# power_supply.net
KiCad netlist of a schematic drawn in Altium Designer
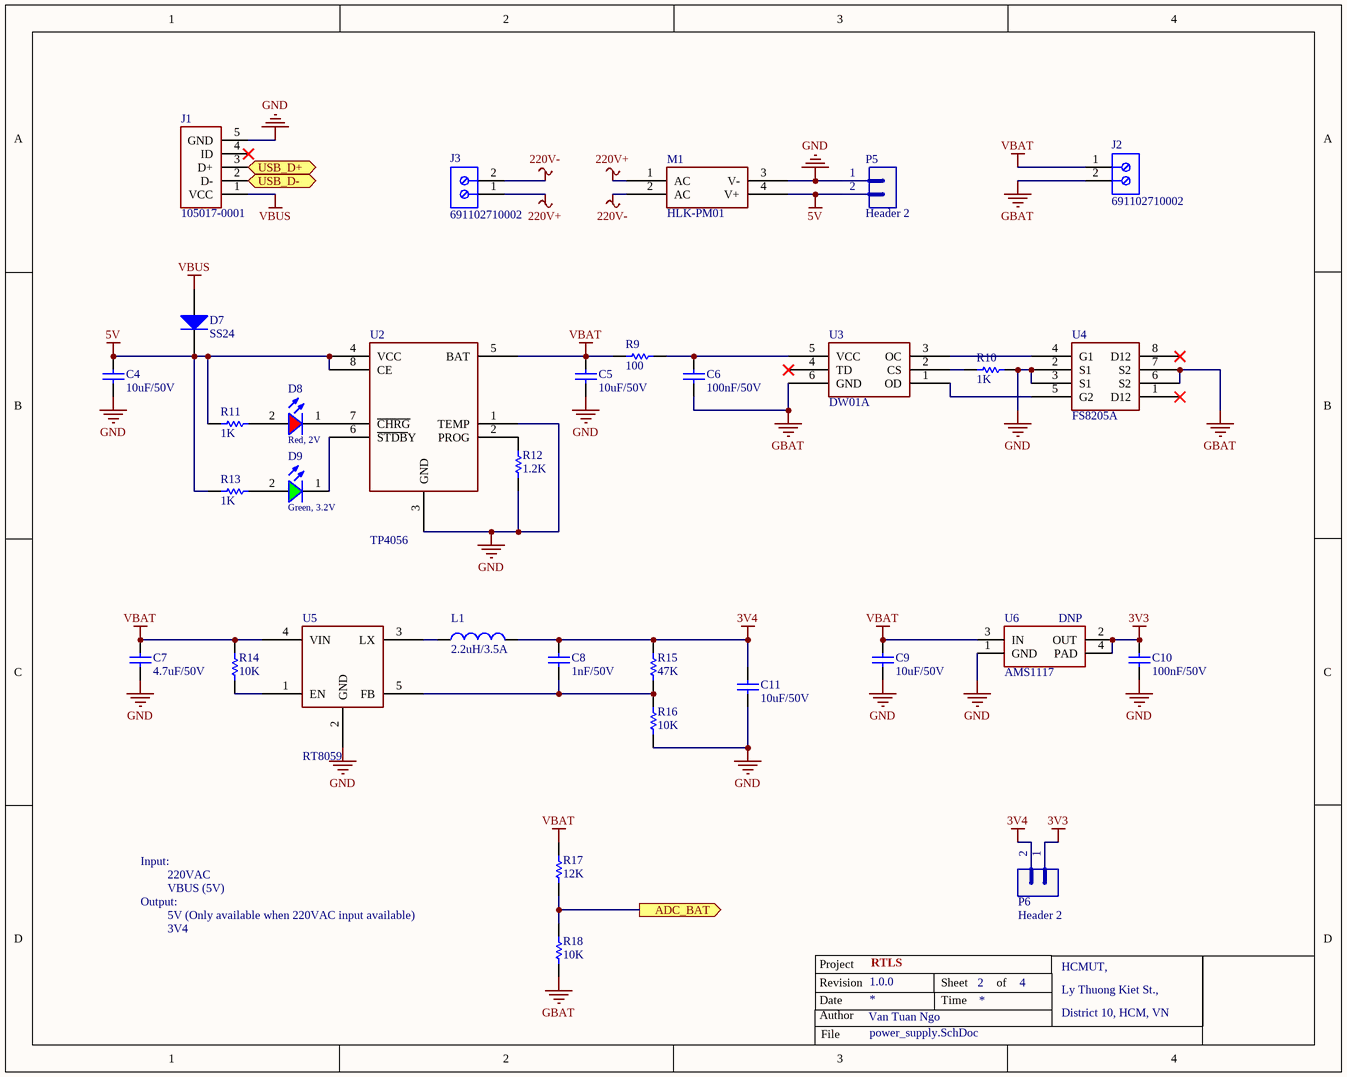
[diagram p0: power_supply.SchDoc]

(export (version "E")
  (design (tool "Eeschema 10.0.6"))
  (components
    (comp (ref "C4")
      (value "10uF/50V")
      (footprint "CAP-SM-0805")
      (description "CAP CER 10UF 50V X5R 0805")
      (fields
        (field (name "MANUFACTURER") "Yageo")
        (field (name "MANUFACTURER PART NUMBER") "CC0805KKX5R9BB106")
      )
      (libsource (lib "capacitor-smd") (part "Cap-10uF-50V-0805"))
    )
    (comp (ref "C5")
      (value "10uF/50V")
      (footprint "CAP-SM-0805")
      (description "CAP CER 10UF 50V X5R 0805")
      (fields
        (field (name "MANUFACTURER") "Yageo")
        (field (name "MANUFACTURER PART NUMBER") "CC0805KKX5R9BB106")
      )
      (libsource (lib "capacitor-smd") (part "Cap-10uF-50V-0805"))
    )
    (comp (ref "C6")
      (value "100nF/50V")
      (footprint "CAP-SM-0805")
      (description "CAP CER 0.1UF 50V Y5V 0805")
      (fields
        (field (name "MANUFACTURER") "Samsung Electro-Mechanics")
        (field (name "MANUFACTURER PART NUMBER") "CL21F104ZBCNNNC")
      )
      (libsource (lib "capacitor-smd") (part "Cap-100nF-50V-0805"))
    )
    (comp (ref "C7")
      (value "4.7uF/50V")
      (footprint "CAP-SM-0805")
      (description "CAP CER 4.7UF 50V X5R 0805")
      (fields
        (field (name "MANUFACTURER") "Murata Electronics")
        (field (name "MANUFACTURER PART NUMBER") "GRM21BR61H475KE51L")
      )
      (libsource (lib "capacitor-smd") (part "Cap-4.7uF-50V-0805"))
    )
    (comp (ref "C8")
      (value "1nF/50V")
      (footprint "CAP-SM-0805")
      (description "CAP CER 22PF 100V X7R 0805")
      (fields
        (field (name "MANUFACTURER") "Johanson Dielectrics Inc.")
        (field (name "MANUFACTURER PART NUMBER") "101X15W102MV4E")
      )
      (libsource (lib "capacitor-smd") (part "Cap-22pF-50V-0805"))
    )
    (comp (ref "C9")
      (value "10uF/50V")
      (footprint "CAP-SM-0805")
      (description "CAP CER 10UF 50V X5R 0805")
      (fields
        (field (name "MANUFACTURER") "Yageo")
        (field (name "MANUFACTURER PART NUMBER") "CC0805KKX5R9BB106")
      )
      (libsource (lib "capacitor-smd") (part "Cap-10uF-50V-0805"))
    )
    (comp (ref "C10")
      (value "100nF/50V")
      (footprint "CAP-SM-0805")
      (description "CAP CER 0.1UF 50V Y5V 0805")
      (fields
        (field (name "MANUFACTURER") "Samsung Electro-Mechanics")
        (field (name "MANUFACTURER PART NUMBER") "CL21F104ZBCNNNC")
      )
      (libsource (lib "capacitor-smd") (part "Cap-100nF-50V-0805"))
    )
    (comp (ref "C11")
      (value "10uF/50V")
      (footprint "CAP-SM-0805")
      (description "CAP CER 10UF 50V X5R 0805")
      (fields
        (field (name "MANUFACTURER") "Yageo")
        (field (name "MANUFACTURER PART NUMBER") "CC0805KKX5R9BB106")
      )
      (libsource (lib "capacitor-smd") (part "Cap-10uF-50V-0805"))
    )
    (comp (ref "D7")
      (value "SS24")
      (footprint "SS24")
      (description "DIODE SCHOTTKY 40V 2A DO214AA")
      (fields (field (name "MANUFACTURER") "ON Semiconductor"))
      (libsource (lib "diode-smd") (part "Diode-SS24"))
    )
    (comp (ref "D8")
      (value "Red, 2V")
      (footprint "WL-SMCW_0805")
      (description "WL-SMCW SMT Mono-color Chip LED Waterclear, size 0805, Red, 2V, 140deg")
      (fields (field (name "PART NUMBER") "150080RS75000") (field (name "PUBLISHER") "Wurth Elektronik"))
      (libsource (lib "led-smd-0805") (part "150080RS75000"))
    )
    (comp (ref "D9")
      (value "Green, 3.2V")
      (footprint "WL-SMCW_0805")
      (description "WL-SMCW SMT Mono-color Chip LED Waterclear, size 0805, Green, 3.2V, 140deg")
      (fields (field (name "PART NUMBER") "150080GS75000") (field (name "PUBLISHER") "Wurth Elektronik"))
      (libsource (lib "led-smd-0805") (part "150080GS75000"))
    )
    (comp (ref "J1")
      (value "105017-0001")
      (footprint "Micro-USB-Female")
      (description "CONN RCPT USB2.0 MICRO B SMD R/A")
      (fields
        (field (name "LOCAL SUPPLIER PART NUMBER") "x")
        (field (name "COPYRIGHT") "Copyright (C) 2018 Accelerated Designs. All rights reserved")
      )
      (libsource (lib "header-connector") (part "Micro-USB-Female"))
    )
    (comp (ref "J2")
      (value "691102710002")
      (footprint "691102710002")
      (description "WR-TBL Serie 102 Horizontal Entry Modular, Pressure Clamp, pitch 5mm, 2p")
      (fields (field (name "PUBLISHER") "Wurth Elektronik"))
      (libsource (lib "domino-wire-protector") (part "691102710002"))
    )
    (comp (ref "J3")
      (value "691102710002")
      (footprint "691102710002")
      (description "WR-TBL Serie 102 Horizontal Entry Modular, Pressure Clamp, pitch 5mm, 2p")
      (fields (field (name "PUBLISHER") "Wurth Elektronik"))
      (libsource (lib "WR-TBL_Wire Protector") (part "691102710002"))
    )
    (comp (ref "L1")
      (value "2.2uH/3.5A")
      (footprint "CD53")
      (libsource (lib "inductor-smd") (part "ind-2.2uH-3.5A-CD53"))
    )
    (comp (ref "M1")
      (value "HLK-PM01")
      (footprint "HLK-PM01")
      (libsource (lib "power-ic-module") (part "HLK-PM01"))
    )
    (comp (ref "P5")
      (value "Header 2")
      (footprint "JP2")
      (description "Header, 2-Pin")
      (fields (field (name "LOCAL SUPPLIER PART NUMBER") "x") (field (name "PUBLISHER") "Altium Limited"))
      (libsource (lib "header-connector") (part "Header 2"))
    )
    (comp (ref "P6")
      (value "Header 2")
      (footprint "JP2")
      (description "Header, 2-Pin")
      (fields (field (name "LOCAL SUPPLIER PART NUMBER") "x") (field (name "PUBLISHER") "Altium Limited"))
      (libsource (lib "") (part "Header 2_1"))
    )
    (comp (ref "R9")
      (value "100")
      (footprint "resistor-smd:RES-SM-0805")
      (description "RES 100 OHM 0.1% 1/5W 0805")
      (fields
        (field (name "MANUFACTURER") "Vishay Thin Film")
        (field (name "MANUFACTURER PART NUMBER") "PTN0805E10R0BST1")
      )
      (libsource (lib "resistor-smd") (part "Res-100-0805"))
    )
    (comp (ref "R10")
      (value "1K")
      (footprint "resistor-smd:RES-SM-0805")
      (description "RES 1K OHM 1% 1/4W 0805")
      (fields
        (field (name "MANUFACTURER") "Stackpole Electronics Inc")
        (field (name "MANUFACTURER PART NUMBER") "RNCP0805FTD1K00")
      )
      (libsource (lib "resistor-smd") (part "Res-1K-0805"))
    )
    (comp (ref "R11")
      (value "1K")
      (footprint "resistor-smd:RES-SM-0805")
      (description "RES 1K OHM 1% 1/4W 0805")
      (fields
        (field (name "MANUFACTURER") "Stackpole Electronics Inc")
        (field (name "MANUFACTURER PART NUMBER") "RNCP0805FTD1K00")
      )
      (libsource (lib "resistor-smd") (part "Res-1K-0805"))
    )
    (comp (ref "R12")
      (value "1.2K")
      (footprint "resistor-smd:RES-SM-0805")
      (description "RES SMD 1.2K OHM 1% 1/8W 0805")
      (fields
        (field (name "MANUFACTURER") "TE Connectivity Passive Product")
        (field (name "MANUFACTURER PART NUMBER") "CRG0805F1K2")
      )
      (libsource (lib "resistor-smd") (part "Res-1.2K-0805"))
    )
    (comp (ref "R13")
      (value "1K")
      (footprint "resistor-smd:RES-SM-0805")
      (description "RES 1K OHM 1% 1/4W 0805")
      (fields
        (field (name "MANUFACTURER") "Stackpole Electronics Inc")
        (field (name "MANUFACTURER PART NUMBER") "RNCP0805FTD1K00")
      )
      (libsource (lib "resistor-smd") (part "Res-1K-0805"))
    )
    (comp (ref "R14")
      (value "10K")
      (footprint "resistor-smd:RES-SM-0805")
      (description "RES 10K OHM 1% 1/4W 0805")
      (fields
        (field (name "MANUFACTURER") "Stackpole Electronics Inc")
        (field (name "MANUFACTURER PART NUMBER") "RNCP0805FTD10K0")
      )
      (libsource (lib "resistor-smd") (part "Res-10k-0805"))
    )
    (comp (ref "R15")
      (value "47K")
      (footprint "resistor-smd:RES-SM-0805")
      (description "RES SMD 47K OHM 1% 1/8W 0805")
      (fields
        (field (name "MANUFACTURER") "Yageo")
        (field (name "MANUFACTURER PART NUMBER") "RC0805FR-0747KL")
      )
      (libsource (lib "resistor-smd") (part "Res-47K-0805"))
    )
    (comp (ref "R16")
      (value "10K")
      (footprint "resistor-smd:RES-SM-0805")
      (description "RES 10K OHM 1% 1/4W 0805")
      (fields
        (field (name "MANUFACTURER") "Stackpole Electronics Inc")
        (field (name "MANUFACTURER PART NUMBER") "RNCP0805FTD10K0")
      )
      (libsource (lib "resistor-smd") (part "Res-10k-0805"))
    )
    (comp (ref "R17")
      (value "12K")
      (footprint "resistor-smd:RES-SM-0805")
      (description "RES 12 KOHM JUMPER 0805")
      (fields
        (field (name "MANUFACTURER") "Vishay Thin Film")
        (field (name "MANUFACTURER PART NUMBER") "PAT0805E3121BST1")
      )
      (libsource (lib "resistor-smd") (part "Res-12K-0805"))
    )
    (comp (ref "R18")
      (value "10K")
      (footprint "resistor-smd:RES-SM-0805")
      (description "RES 10K OHM 1% 1/4W 0805")
      (fields
        (field (name "MANUFACTURER") "Stackpole Electronics Inc")
        (field (name "MANUFACTURER PART NUMBER") "RNCP0805FTD10K0")
      )
      (libsource (lib "resistor-smd") (part "Res-10k-0805"))
    )
    (comp (ref "U2")
      (value "TP4056")
      (footprint "SOP8")
      (description "Linear charger for single cell\r\nlithium-ion batteries")
      (libsource (lib "power-ic-module") (part "TP4056"))
    )
    (comp (ref "U3")
      (value "DW01A")
      (footprint "SOT-23-6")
      (description "Battery protection IC")
      (libsource (lib "power-ic-module") (part "DW01A"))
    )
    (comp (ref "U4") (value "FS8205A") (footprint "TSSOP8") (libsource (lib "mosfet-smd") (part "FS8205A")))
    (comp (ref "U5")
      (value "RT8059")
      (footprint "SOT-23-5")
      (description "High efficiency PWM step-down DC/DC converter")
      (libsource (lib "power-ic-module") (part "RT8059"))
    )
    (comp (ref "U6")
      (value "AMS1117")
      (footprint "SOT223")
      (description "Available in 1.8V, 2.5V, 2.85V, 3.3V, 5V, and  Adjustable Versions")
      (libsource (lib "power-ic-module") (part "AMS1117"))
    )
  )
  (nets
    (net (code "1") (name "/ADC_BAT") (class "Default")
      (node (ref "R17") (pin "1") (pinfunction "1_1") (pintype "passive"))
      (node (ref "R18") (pin "2") (pinfunction "2_2") (pintype "passive"))
    )
    (net (code "2") (name "/USB_D+") (class "Default")
      (node (ref "J1") (pin "3") (pinfunction "D+_3") (pintype "passive"))
    )
    (net (code "3") (name "/USB_D-") (class "Default")
      (node (ref "J1") (pin "2") (pinfunction "D-_2") (pintype "passive"))
    )
    (net (code "4") (name "3V3") (class "Default")
      (node (ref "C10") (pin "2") (pinfunction "2_2") (pintype "passive"))
      (node (ref "P6") (pin "1") (pinfunction "1_1") (pintype "passive"))
      (node (ref "U6") (pin "2") (pinfunction "OUT_2") (pintype "passive"))
      (node (ref "U6") (pin "4") (pinfunction "PAD_4") (pintype "passive"))
    )
    (net (code "5") (name "3V4") (class "Default")
      (node (ref "C11") (pin "2") (pinfunction "2_2") (pintype "passive"))
      (node (ref "C8") (pin "2") (pinfunction "2_2") (pintype "passive"))
      (node (ref "L1") (pin "2") (pinfunction "2_2") (pintype "passive"))
      (node (ref "P6") (pin "2") (pinfunction "2_2") (pintype "passive"))
      (node (ref "R15") (pin "2") (pinfunction "2_2") (pintype "passive"))
    )
    (net (code "6") (name "5V") (class "Default")
      (node (ref "C4") (pin "2") (pinfunction "2_2") (pintype "passive"))
      (node (ref "D7") (pin "1") (pinfunction "K_1") (pintype "passive"))
      (node (ref "M1") (pin "4") (pinfunction "V+_4") (pintype "passive"))
      (node (ref "P5") (pin "2") (pinfunction "2_2") (pintype "passive"))
      (node (ref "R11") (pin "1") (pinfunction "1_1") (pintype "passive"))
      (node (ref "R13") (pin "1") (pinfunction "1_1") (pintype "passive"))
      (node (ref "U2") (pin "4") (pinfunction "VCC_4") (pintype "passive"))
      (node (ref "U2") (pin "8") (pinfunction "CE_8") (pintype "passive"))
    )
    (net (code "7") (name "220V+") (class "Default")
      (node (ref "J3") (pin "1") (pinfunction "1_1") (pintype "passive"))
      (node (ref "M1") (pin "1") (pinfunction "AC_1") (pintype "passive"))
    )
    (net (code "8") (name "220V-") (class "Default")
      (node (ref "J3") (pin "2") (pinfunction "2_2") (pintype "passive"))
      (node (ref "M1") (pin "2") (pinfunction "AC_2") (pintype "passive"))
    )
    (net (code "9") (name "GBAT") (class "Default")
      (node (ref "C6") (pin "1") (pinfunction "1_1") (pintype "passive"))
      (node (ref "J2") (pin "2") (pinfunction "2_2") (pintype "passive"))
      (node (ref "R18") (pin "1") (pinfunction "1_1") (pintype "passive"))
      (node (ref "U3") (pin "6") (pinfunction "GND_6") (pintype "passive"))
      (node (ref "U4") (pin "6") (pinfunction "S2_6") (pintype "passive"))
      (node (ref "U4") (pin "7") (pinfunction "S2_7") (pintype "passive"))
    )
    (net (code "10") (name "GND") (class "Default")
      (node (ref "C10") (pin "1") (pinfunction "1_1") (pintype "passive"))
      (node (ref "C11") (pin "1") (pinfunction "1_1") (pintype "passive"))
      (node (ref "C4") (pin "1") (pinfunction "1_1") (pintype "passive"))
      (node (ref "C5") (pin "1") (pinfunction "1_1") (pintype "passive"))
      (node (ref "C7") (pin "1") (pinfunction "1_1") (pintype "passive"))
      (node (ref "C9") (pin "1") (pinfunction "1_1") (pintype "passive"))
      (node (ref "J1") (pin "5") (pinfunction "GND_5") (pintype "passive"))
      (node (ref "M1") (pin "3") (pinfunction "V-_3") (pintype "passive"))
      (node (ref "P5") (pin "1") (pinfunction "1_1") (pintype "passive"))
      (node (ref "R10") (pin "2") (pinfunction "2_2") (pintype "passive"))
      (node (ref "R12") (pin "1") (pinfunction "1_1") (pintype "passive"))
      (node (ref "R16") (pin "1") (pinfunction "1_1") (pintype "passive"))
      (node (ref "U2") (pin "1") (pinfunction "TEMP_1") (pintype "passive"))
      (node (ref "U2") (pin "3") (pinfunction "GND_3") (pintype "passive"))
      (node (ref "U4") (pin "2") (pinfunction "S1_2") (pintype "passive"))
      (node (ref "U4") (pin "3") (pinfunction "S1_3") (pintype "passive"))
      (node (ref "U5") (pin "2") (pinfunction "GND_2") (pintype "passive"))
      (node (ref "U6") (pin "1") (pinfunction "GND_1") (pintype "passive"))
    )
    (net (code "11") (name "Net-(D8-A)") (class "Default")
      (node (ref "D8") (pin "2") (pinfunction "A_2") (pintype "passive"))
      (node (ref "R11") (pin "2") (pinfunction "2_2") (pintype "passive"))
    )
    (net (code "12") (name "Net-(D8-K)") (class "Default")
      (node (ref "D8") (pin "1") (pinfunction "K_1") (pintype "passive"))
      (node (ref "U2") (pin "7") (pinfunction "~{CHRG}_7") (pintype "passive"))
    )
    (net (code "13") (name "Net-(D9-A)") (class "Default")
      (node (ref "D9") (pin "2") (pinfunction "A_2") (pintype "passive"))
      (node (ref "R13") (pin "2") (pinfunction "2_2") (pintype "passive"))
    )
    (net (code "14") (name "Net-(D9-K)") (class "Default")
      (node (ref "D9") (pin "1") (pinfunction "K_1") (pintype "passive"))
      (node (ref "U2") (pin "6") (pinfunction "~{STDB}Y_6") (pintype "passive"))
    )
    (net (code "15") (name "Net-(U2-PROG)") (class "Default")
      (node (ref "R12") (pin "2") (pinfunction "2_2") (pintype "passive"))
      (node (ref "U2") (pin "2") (pinfunction "PROG_2") (pintype "passive"))
    )
    (net (code "16") (name "Net-(U3-CS)") (class "Default")
      (node (ref "R10") (pin "1") (pinfunction "1_1") (pintype "passive"))
      (node (ref "U3") (pin "2") (pinfunction "CS_2") (pintype "passive"))
    )
    (net (code "17") (name "Net-(U3-OC)") (class "Default")
      (node (ref "U3") (pin "3") (pinfunction "OC_3") (pintype "passive"))
      (node (ref "U4") (pin "4") (pinfunction "G1_4") (pintype "passive"))
    )
    (net (code "18") (name "Net-(U3-OD)") (class "Default")
      (node (ref "U3") (pin "1") (pinfunction "OD_1") (pintype "passive"))
      (node (ref "U4") (pin "5") (pinfunction "G2_5") (pintype "passive"))
    )
    (net (code "19") (name "Net-(U3-VCC)") (class "Default")
      (node (ref "C6") (pin "2") (pinfunction "2_2") (pintype "passive"))
      (node (ref "R9") (pin "2") (pinfunction "2_2") (pintype "passive"))
      (node (ref "U3") (pin "5") (pinfunction "VCC_5") (pintype "passive"))
    )
    (net (code "20") (name "Net-(U5-EN)") (class "Default")
      (node (ref "R14") (pin "1") (pinfunction "1_1") (pintype "passive"))
      (node (ref "U5") (pin "1") (pinfunction "EN_1") (pintype "passive"))
    )
    (net (code "21") (name "Net-(U5-FB)") (class "Default")
      (node (ref "C8") (pin "1") (pinfunction "1_1") (pintype "passive"))
      (node (ref "R15") (pin "1") (pinfunction "1_1") (pintype "passive"))
      (node (ref "R16") (pin "2") (pinfunction "2_2") (pintype "passive"))
      (node (ref "U5") (pin "5") (pinfunction "FB_5") (pintype "passive"))
    )
    (net (code "22") (name "Net-(U5-LX)") (class "Default")
      (node (ref "L1") (pin "1") (pinfunction "1_1") (pintype "passive"))
      (node (ref "U5") (pin "3") (pinfunction "LX_3") (pintype "passive"))
    )
    (net (code "23") (name "VBAT") (class "Default")
      (node (ref "C5") (pin "2") (pinfunction "2_2") (pintype "passive"))
      (node (ref "C7") (pin "2") (pinfunction "2_2") (pintype "passive"))
      (node (ref "C9") (pin "2") (pinfunction "2_2") (pintype "passive"))
      (node (ref "J2") (pin "1") (pinfunction "1_1") (pintype "passive"))
      (node (ref "R14") (pin "2") (pinfunction "2_2") (pintype "passive"))
      (node (ref "R17") (pin "2") (pinfunction "2_2") (pintype "passive"))
      (node (ref "R9") (pin "1") (pinfunction "1_1") (pintype "passive"))
      (node (ref "U2") (pin "5") (pinfunction "BAT_5") (pintype "passive"))
      (node (ref "U5") (pin "4") (pinfunction "VIN_4") (pintype "passive"))
      (node (ref "U6") (pin "3") (pinfunction "IN_3") (pintype "passive"))
    )
    (net (code "24") (name "VBUS") (class "Default")
      (node (ref "D7") (pin "2") (pinfunction "A_2") (pintype "passive"))
      (node (ref "J1") (pin "1") (pinfunction "VCC_1") (pintype "power_in"))
    )
    (net (code "25") (name "unconnected-(J1-ID-Pad4)") (class "Default")
      (node (ref "J1") (pin "4") (pinfunction "ID_4") (pintype "passive+no_connect"))
    )
    (net (code "26") (name "unconnected-(U3-TD-Pad4)") (class "Default")
      (node (ref "U3") (pin "4") (pinfunction "TD_4") (pintype "passive+no_connect"))
    )
    (net (code "27") (name "unconnected-(U4-D12-Pad1)") (class "Default")
      (node (ref "U4") (pin "1") (pinfunction "D12_1") (pintype "passive+no_connect"))
    )
    (net (code "28") (name "unconnected-(U4-D12-Pad8)") (class "Default")
      (node (ref "U4") (pin "8") (pinfunction "D12_8") (pintype "passive+no_connect"))
    )
  )
)
